# v8_psp.net
KiCad netlist of a schematic drawn in EAGLE
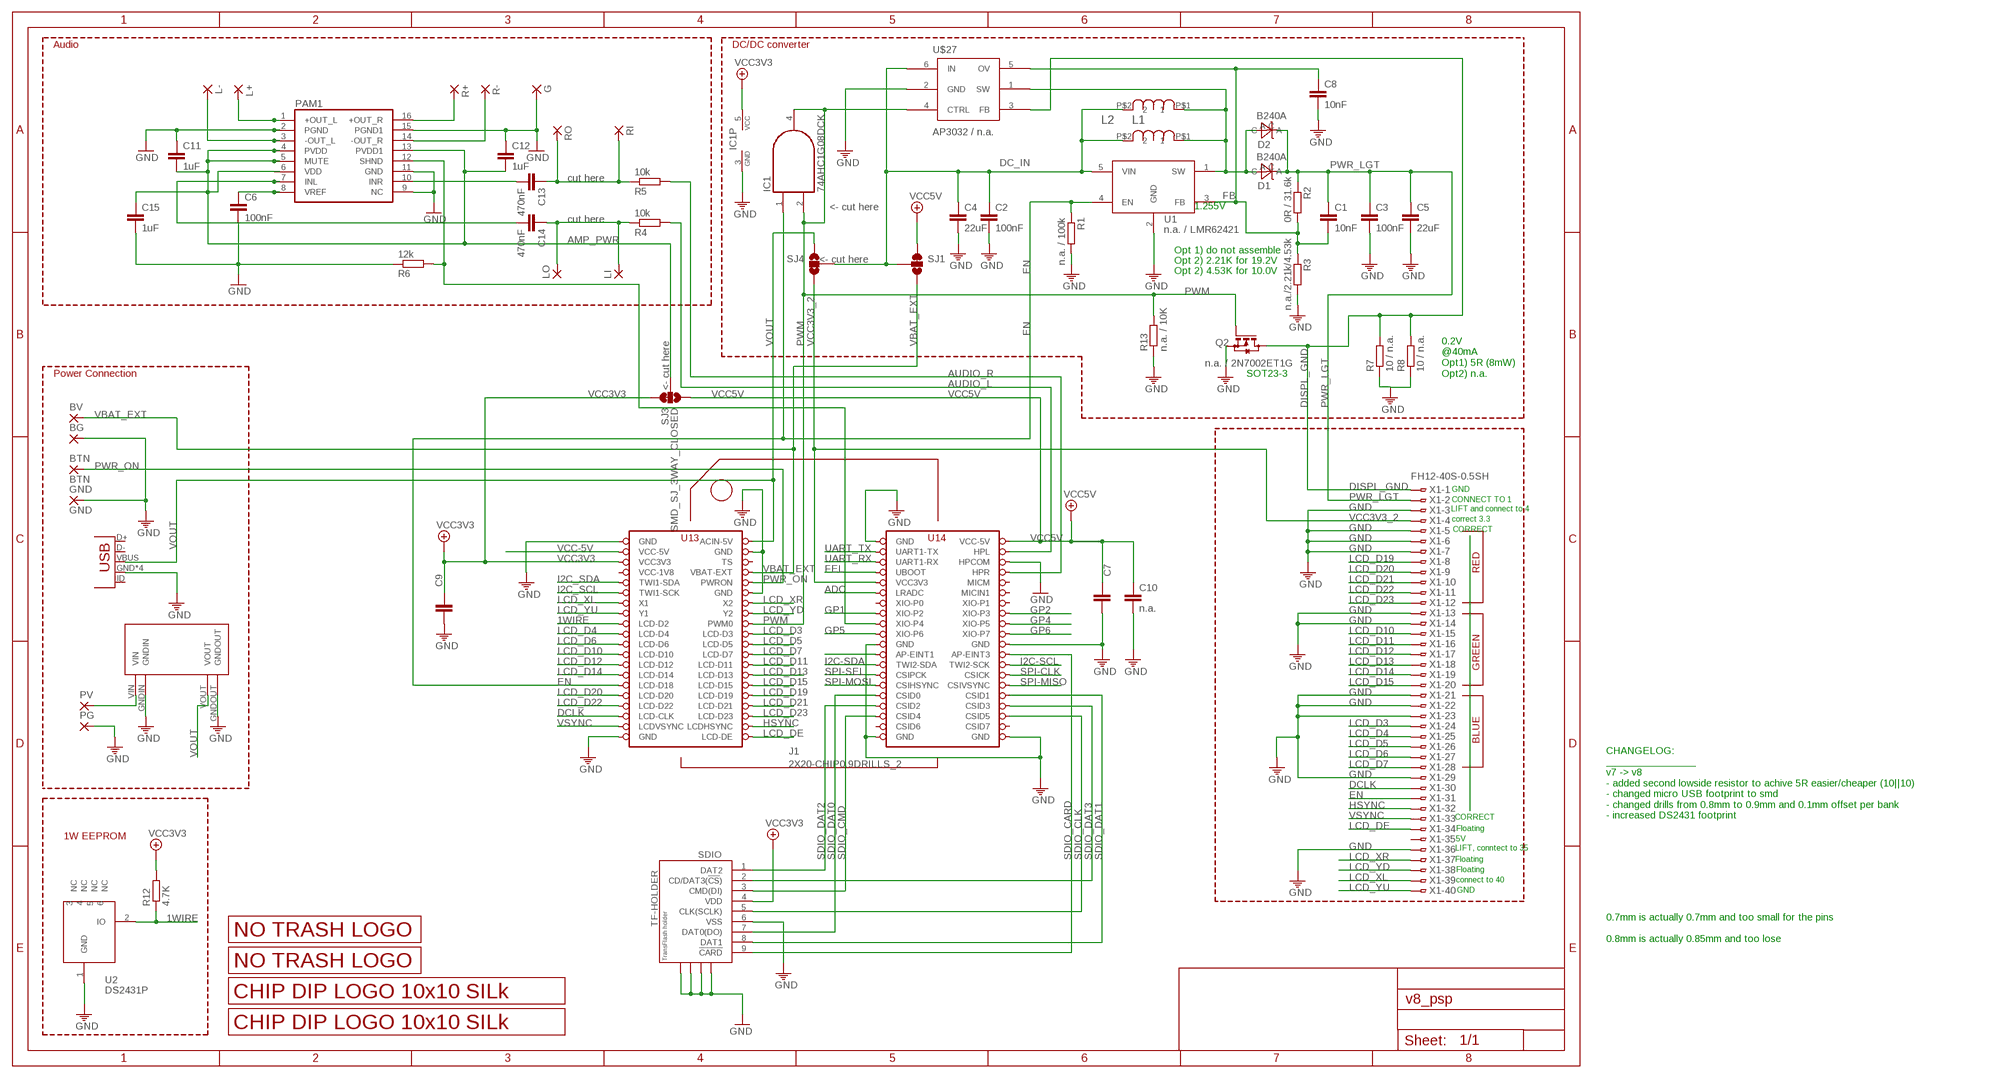
[diagram p0: schematic, sheet 1]

(export (version "E")
  (design (tool "Eeschema 10.0.6"))
  (components
    (comp (ref "BG")
      (value "1,6/0,8")
      (footprint "eagle-import:1,6_0,8")
      (libsource (lib "eagle-import") (part "1,6/0,8"))
    )
    (comp (ref "BTN")
      (value "BTN")
      (footprint "eagle-import:SMD1,27-2,54")
      (libsource (lib "eagle-import") (part "SMD2"))
    )
    (comp (ref "BV")
      (value "1,6/0,8")
      (footprint "eagle-import:1,6_0,8")
      (libsource (lib "eagle-import") (part "1,6/0,8"))
    )
    (comp (ref "C1")
      (value "10nF")
      (footprint "eagle-import:C0805")
      (libsource (lib "eagle-import") (part "C-EUC0805"))
    )
    (comp (ref "C2")
      (value "100nF")
      (footprint "eagle-import:C0805")
      (libsource (lib "eagle-import") (part "C-EUC0805"))
    )
    (comp (ref "C3")
      (value "100nF")
      (footprint "eagle-import:C0805")
      (libsource (lib "eagle-import") (part "C-EUC0805"))
    )
    (comp (ref "C4")
      (value "22uF")
      (footprint "eagle-import:C1206")
      (libsource (lib "eagle-import") (part "C-EUC1206"))
    )
    (comp (ref "C5")
      (value "22uF")
      (footprint "eagle-import:C1206")
      (libsource (lib "eagle-import") (part "C-EUC1206"))
    )
    (comp (ref "C6")
      (value "100nF")
      (footprint "eagle-import:C0805")
      (libsource (lib "eagle-import") (part "C-EUC0805"))
    )
    (comp (ref "C7")
      (value "n.a.")
      (footprint "eagle-import:C0805")
      (libsource (lib "eagle-import") (part "C-EUC0805"))
    )
    (comp (ref "C8")
      (value "10nF")
      (footprint "eagle-import:C0805")
      (libsource (lib "eagle-import") (part "C-EUC0805"))
    )
    (comp (ref "C9")
      (value "n.a.")
      (footprint "eagle-import:C0805")
      (libsource (lib "eagle-import") (part "C-EUC0805"))
    )
    (comp (ref "C10")
      (value "n.a.")
      (footprint "eagle-import:C0805")
      (libsource (lib "eagle-import") (part "C-EUC0805"))
    )
    (comp (ref "C11")
      (value "1uF")
      (footprint "eagle-import:C0805")
      (libsource (lib "eagle-import") (part "C-EUC0805"))
    )
    (comp (ref "C12")
      (value "1uF")
      (footprint "eagle-import:C0805")
      (libsource (lib "eagle-import") (part "C-EUC0805"))
    )
    (comp (ref "C13")
      (value "470nF")
      (footprint "eagle-import:C0805")
      (libsource (lib "eagle-import") (part "C-EUC0805"))
    )
    (comp (ref "C14")
      (value "470nF")
      (footprint "eagle-import:C0805")
      (libsource (lib "eagle-import") (part "C-EUC0805"))
    )
    (comp (ref "C15")
      (value "1uF")
      (footprint "eagle-import:C0805")
      (libsource (lib "eagle-import") (part "C-EUC0805"))
    )
    (comp (ref "D1")
      (value "B240A")
      (footprint "eagle-import:DO-214AC")
      (fields (field (name "MFG") "DIGIKEY") (field (name "VENDOR_PART_NUMBER") "B240A-13-F"))
      (libsource (lib "eagle-import") (part "DIODE_SCHTKY_B240"))
    )
    (comp (ref "D2")
      (value "B240A")
      (footprint "eagle-import:DO-214AC")
      (fields (field (name "MFG") "DIGIKEY") (field (name "VENDOR_PART_NUMBER") "B240A-13-F"))
      (libsource (lib "eagle-import") (part "DIODE_SCHTKY_B240"))
    )
    (comp (ref "G")
      (value "1,6/0,8")
      (footprint "eagle-import:1,6_0,8")
      (libsource (lib "eagle-import") (part "1,6/0,8"))
    )
    (comp (ref "GND")
      (value "GND")
      (footprint "eagle-import:SMD1,27-2,54")
      (libsource (lib "eagle-import") (part "SMD2"))
    )
    (comp (ref "IC1")
      (value "74AHC1G08DCK")
      (footprint "eagle-import:SC70-5")
      (libsource (lib "eagle-import") (part "741G08DCKAHC"))
    )
    (comp (ref "J1")
      (value "2X20-CHIP0.9DRILLS_2")
      (footprint "eagle-import:2X20CHIP_BANK_OFFSET_TH_0.9")
      (libsource (lib "eagle-import") (part "2X20-CHIP0.9DRILLS_2"))
    )
    (comp (ref "JP1")
      (value "USBMICRO_SMD")
      (footprint "eagle-import:USB-B-MICRO-SMD_V03")
      (libsource (lib "eagle-import") (part "USBMICRO_SMD"))
    )
    (comp (ref "L+")
      (value "1,6/0,8")
      (footprint "eagle-import:1,6_0,8")
      (libsource (lib "eagle-import") (part "1,6/0,8"))
    )
    (comp (ref "L-")
      (value "1,6/0,8")
      (footprint "eagle-import:1,6_0,8")
      (libsource (lib "eagle-import") (part "1,6/0,8"))
    )
    (comp (ref "L1")
      (value "SRN6045-100M")
      (footprint "eagle-import:SRN6045")
      (fields (field (name "MFG") "DIGIKEY"))
      (libsource (lib "eagle-import") (part "SRN6045-100M"))
    )
    (comp (ref "L2")
      (value "SRN6045-100M")
      (footprint "eagle-import:SRN6045")
      (fields (field (name "MFG") "DIGIKEY"))
      (libsource (lib "eagle-import") (part "SRN6045-100M"))
    )
    (comp (ref "LI")
      (value "1,6/0,8")
      (footprint "eagle-import:1,6_0,8")
      (libsource (lib "eagle-import") (part "1,6/0,8"))
    )
    (comp (ref "LO")
      (value "1,6/0,8")
      (footprint "eagle-import:1,6_0,8")
      (libsource (lib "eagle-import") (part "1,6/0,8"))
    )
    (comp (ref "PAM1")
      (value "PAM8403")
      (footprint "eagle-import:SOP-16")
      (libsource (lib "eagle-import") (part "PAM8403"))
    )
    (comp (ref "PG")
      (value "1,6/0,8")
      (footprint "eagle-import:1,6_0,8")
      (libsource (lib "eagle-import") (part "1,6/0,8"))
    )
    (comp (ref "PV")
      (value "1,6/0,8")
      (footprint "eagle-import:1,6_0,8")
      (libsource (lib "eagle-import") (part "1,6/0,8"))
    )
    (comp (ref "Q2")
      (value "n.a. / 2N7002ET1G")
      (footprint "eagle-import:SOT23")
      (libsource (lib "eagle-import") (part "BSS123"))
    )
    (comp (ref "R+")
      (value "1,6/0,8")
      (footprint "eagle-import:1,6_0,8")
      (libsource (lib "eagle-import") (part "1,6/0,8"))
    )
    (comp (ref "R-")
      (value "1,6/0,8")
      (footprint "eagle-import:1,6_0,8")
      (libsource (lib "eagle-import") (part "1,6/0,8"))
    )
    (comp (ref "R1")
      (value "n.a. / 100k")
      (footprint "eagle-import:M0805")
      (libsource (lib "eagle-import") (part "R-EU_M0805"))
    )
    (comp (ref "R2")
      (value "0R / 31.6k")
      (footprint "eagle-import:M0805")
      (libsource (lib "eagle-import") (part "R-EU_M0805"))
    )
    (comp (ref "R3")
      (value "n.a./2.21k/4.53k")
      (footprint "eagle-import:M0805")
      (libsource (lib "eagle-import") (part "R-EU_M0805"))
    )
    (comp (ref "R4")
      (value "10k")
      (footprint "eagle-import:R0805")
      (libsource (lib "eagle-import") (part "R-EU_R0805"))
    )
    (comp (ref "R5")
      (value "10k")
      (footprint "eagle-import:R0805")
      (libsource (lib "eagle-import") (part "R-EU_R0805"))
    )
    (comp (ref "R6")
      (value "12k")
      (footprint "eagle-import:R0805")
      (libsource (lib "eagle-import") (part "R-EU_R0805"))
    )
    (comp (ref "R7")
      (value "10 / n.a.")
      (footprint "eagle-import:M0805")
      (libsource (lib "eagle-import") (part "R-EU_M0805"))
    )
    (comp (ref "R8")
      (value "10 / n.a.")
      (footprint "eagle-import:M0805")
      (libsource (lib "eagle-import") (part "R-EU_M0805"))
    )
    (comp (ref "R12")
      (value "4.7K")
      (footprint "eagle-import:M0805")
      (libsource (lib "eagle-import") (part "R-EU_M0805"))
    )
    (comp (ref "R13")
      (value "n.a. / 10K")
      (footprint "eagle-import:M0805")
      (libsource (lib "eagle-import") (part "R-EU_M0805"))
    )
    (comp (ref "RI")
      (value "1,6/0,8")
      (footprint "eagle-import:1,6_0,8")
      (libsource (lib "eagle-import") (part "1,6/0,8"))
    )
    (comp (ref "RO")
      (value "1,6/0,8")
      (footprint "eagle-import:1,6_0,8")
      (libsource (lib "eagle-import") (part "1,6/0,8"))
    )
    (comp (ref "SDIO")
      (value "TF-HOLDER")
      (footprint "eagle-import:TF-PULL")
      (libsource (lib "eagle-import") (part "TF-HOLDER"))
    )
    (comp (ref "SJ1")
      (value "SMD_SJ_3WAY_CLOSED")
      (footprint "eagle-import:SMD_SJ_3WAY_CLOSED")
      (libsource (lib "eagle-import") (part "SMD_SJ_3WAY_CLOSED"))
    )
    (comp (ref "SJ3")
      (value "SMD_SJ_3WAY_CLOSED")
      (footprint "eagle-import:SMD_SJ_3WAY_CLOSED")
      (libsource (lib "eagle-import") (part "SMD_SJ_3WAY_CLOSED"))
    )
    (comp (ref "SJ4")
      (value "SMD_SJ_3WAY_OPENT")
      (footprint "eagle-import:SMD_SJ_3WAY_OPEN")
      (libsource (lib "eagle-import") (part "SMD_SJ_3WAY_OPENT"))
    )
    (comp (ref "U$2")
      (value "LOGO_10X10_SILK")
      (footprint "eagle-import:LOGO2_10X10_SILK")
      (libsource (lib "eagle-import") (part "LOGO_10X10_SILK"))
    )
    (comp (ref "U$3")
      (value "LOGO_NO_TRASHROHS")
      (footprint "eagle-import:LOGO_ROHS_SYM")
      (libsource (lib "eagle-import") (part "LOGO_NO_TRASHROHS"))
    )
    (comp (ref "U$4")
      (value "LOGO_NO_TRASHNO_TRASH")
      (footprint "eagle-import:LOGO_ROHS_NO_TRASH")
      (libsource (lib "eagle-import") (part "LOGO_NO_TRASHNO_TRASH"))
    )
    (comp (ref "U$5")
      (value "LOGO_10X10_SILK")
      (footprint "eagle-import:LOGO2_10X10_SILK")
      (libsource (lib "eagle-import") (part "LOGO_10X10_SILK"))
    )
    (comp (ref "U$10")
      (value "MP1584EN_FRAMELESS")
      (footprint "eagle-import:MP1584EN_FRAMELESS")
      (libsource (lib "eagle-import") (part "MP1584EN_FRAMELESS"))
    )
    (comp (ref "U$27")
      (value "AP3032 / n.a.")
      (footprint "eagle-import:SOT23-6")
      (libsource (lib "eagle-import") (part "AP3032"))
    )
    (comp (ref "U1")
      (value "n.a. / LMR62421")
      (footprint "eagle-import:SOT23-5")
      (fields (field (name "MFG") "DIGIKEY") (field (name "VENDOR_PART_NUMBER") "LMR62421XMFE/NOPB"))
      (libsource (lib "eagle-import") (part "LMR62421"))
    )
    (comp (ref "U2")
      (value "DS2431P")
      (footprint "eagle-import:TSOC6")
      (fields (field (name "MFG") "DIGIKEY") (field (name "VENDOR_PART_NUMBER") "DS2431P+T&R"))
      (libsource (lib "eagle-import") (part "DS2431P"))
    )
    (comp (ref "X1")
      (value "FH12-40S-0.5SH")
      (footprint "eagle-import:FH12-40S-0.5SH")
      (fields (field (name "MFG") "DIGIKEY") (field (name "VENDOR_PART_NUMBER") "FH12-40S-0.5SH(55)"))
      (libsource (lib "eagle-import") (part "FH12-40S-0.5SH"))
    )
  )
  (nets
    (net (code "1") (name "/1WIRE") (class "Default")
      (node (ref "J1") (pin "LCD-D2") (pinfunction "LCD-D2_LCD-D2") (pintype "passive"))
      (node (ref "R12") (pin "1") (pinfunction "1_1") (pintype "passive"))
      (node (ref "U2") (pin "2") (pinfunction "IO_2") (pintype "bidirectional"))
    )
    (net (code "2") (name "/ADC") (class "Default")
      (node (ref "J1") (pin "LRADC") (pinfunction "LRADC_LRADC") (pintype "passive"))
    )
    (net (code "3") (name "/AMP_PWR") (class "Default")
      (node (ref "C11") (pin "2") (pinfunction "2_2") (pintype "passive"))
      (node (ref "C12") (pin "2") (pinfunction "2_2") (pintype "passive"))
      (node (ref "C15") (pin "1") (pinfunction "1_1") (pintype "passive"))
      (node (ref "PAM1") (pin "13") (pinfunction "PVDD1_13") (pintype "output"))
      (node (ref "PAM1") (pin "4") (pinfunction "PVDD_4") (pintype "input"))
      (node (ref "PAM1") (pin "5") (pinfunction "MUTE_5") (pintype "input"))
      (node (ref "PAM1") (pin "6") (pinfunction "VDD_6") (pintype "input"))
      (node (ref "SJ3") (pin "2") (pinfunction "2_2") (pintype "passive"))
    )
    (net (code "4") (name "/AUDIO_L") (class "Default")
      (node (ref "J1") (pin "HPL") (pinfunction "HPL_HPL") (pintype "passive"))
      (node (ref "R4") (pin "2") (pinfunction "2_2") (pintype "passive"))
    )
    (net (code "5") (name "/AUDIO_R") (class "Default")
      (node (ref "J1") (pin "HPR") (pinfunction "HPR_HPR") (pintype "passive"))
      (node (ref "R5") (pin "2") (pinfunction "2_2") (pintype "passive"))
    )
    (net (code "6") (name "/DCLK") (class "Default")
      (node (ref "J1") (pin "LCD-CLK") (pinfunction "LCD-CLK_LCD-CLK") (pintype "passive"))
      (node (ref "X1") (pin "30") (pinfunction "1_30") (pintype "passive"))
    )
    (net (code "7") (name "/DC_IN") (class "Default")
      (node (ref "C2") (pin "1") (pinfunction "1_1") (pintype "passive"))
      (node (ref "C4") (pin "1") (pinfunction "1_1") (pintype "passive"))
      (node (ref "L1") (pin "P$2") (pinfunction "2_P$2") (pintype "passive"))
      (node (ref "L2") (pin "P$2") (pinfunction "2_P$2") (pintype "passive"))
      (node (ref "SJ1") (pin "2") (pinfunction "2_2") (pintype "passive"))
      (node (ref "SJ4") (pin "2") (pinfunction "2_2") (pintype "passive"))
      (node (ref "U$27") (pin "6") (pinfunction "IN_6") (pintype "power_in"))
      (node (ref "U1") (pin "5") (pinfunction "VIN_5") (pintype "bidirectional"))
    )
    (net (code "8") (name "/DISPL_GND") (class "Default")
      (node (ref "Q2") (pin "3") (pinfunction "D_3") (pintype "passive"))
      (node (ref "R7") (pin "2") (pinfunction "2_2") (pintype "passive"))
      (node (ref "R8") (pin "2") (pinfunction "2_2") (pintype "passive"))
      (node (ref "U$27") (pin "3") (pinfunction "FB_3") (pintype "passive"))
      (node (ref "X1") (pin "1") (pinfunction "1_1") (pintype "passive"))
    )
    (net (code "9") (name "/EN") (class "Default")
      (node (ref "IC1") (pin "1") (pinfunction "I0_1") (pintype "input"))
      (node (ref "J1") (pin "LCD-D18") (pinfunction "LCD-D18_LCD-D18") (pintype "passive"))
      (node (ref "R1") (pin "1") (pinfunction "1_1") (pintype "passive"))
      (node (ref "U1") (pin "4") (pinfunction "EN_4") (pintype "bidirectional"))
      (node (ref "X1") (pin "31") (pinfunction "1_31") (pintype "passive"))
    )
    (net (code "10") (name "/FB") (class "Default")
      (node (ref "C1") (pin "2") (pinfunction "2_2") (pintype "passive"))
      (node (ref "C8") (pin "1") (pinfunction "1_1") (pintype "passive"))
      (node (ref "R2") (pin "2") (pinfunction "2_2") (pintype "passive"))
      (node (ref "R3") (pin "1") (pinfunction "1_1") (pintype "passive"))
      (node (ref "U$27") (pin "5") (pinfunction "OV_5") (pintype "power_in"))
      (node (ref "U1") (pin "3") (pinfunction "FB_3") (pintype "bidirectional"))
    )
    (net (code "11") (name "/FEL") (class "Default")
      (node (ref "J1") (pin "FEL") (pinfunction "UBOOT_FEL") (pintype "passive"))
    )
    (net (code "12") (name "/GP1") (class "Default")
      (node (ref "J1") (pin "XIO-P2") (pinfunction "XIO-P2_XIO-P2") (pintype "passive"))
    )
    (net (code "13") (name "/GP2") (class "Default")
      (node (ref "J1") (pin "XIO-P3") (pinfunction "XIO-P3_XIO-P3") (pintype "passive"))
    )
    (net (code "14") (name "/GP4") (class "Default")
      (node (ref "J1") (pin "XIO-P5") (pinfunction "XIO-P5_XIO-P5") (pintype "passive"))
    )
    (net (code "15") (name "/GP5") (class "Default")
      (node (ref "J1") (pin "XIO-P6") (pinfunction "XIO-P6_XIO-P6") (pintype "passive"))
    )
    (net (code "16") (name "/GP6") (class "Default")
      (node (ref "J1") (pin "XIO-P7") (pinfunction "XIO-P7_XIO-P7") (pintype "passive"))
    )
    (net (code "17") (name "/HSYNC") (class "Default")
      (node (ref "J1") (pin "LCD-HSYNC") (pinfunction "LCDHSYNC_LCD-HSYNC") (pintype "passive"))
      (node (ref "X1") (pin "32") (pinfunction "1_32") (pintype "passive"))
    )
    (net (code "18") (name "/I2C-SCL") (class "Default")
      (node (ref "J1") (pin "TWI2-SCK") (pinfunction "TWI2-SCK_TWI2-SCK") (pintype "passive"))
    )
    (net (code "19") (name "/I2C-SDA") (class "Default")
      (node (ref "J1") (pin "TWI2-SDA") (pinfunction "TWI2-SDA_TWI2-SDA") (pintype "passive"))
    )
    (net (code "20") (name "/I2C_SCL") (class "Default")
      (node (ref "J1") (pin "TWI1-SCK") (pinfunction "TWI1-SCK_TWI1-SCK") (pintype "passive"))
    )
    (net (code "21") (name "/I2C_SDA") (class "Default")
      (node (ref "J1") (pin "TWI1-SDA") (pinfunction "TWI1-SDA_TWI1-SDA") (pintype "passive"))
    )
    (net (code "22") (name "/LCD_D3") (class "Default")
      (node (ref "J1") (pin "LCD-D3") (pinfunction "LCD-D3_LCD-D3") (pintype "passive"))
      (node (ref "X1") (pin "24") (pinfunction "1_24") (pintype "passive"))
    )
    (net (code "23") (name "/LCD_D4") (class "Default")
      (node (ref "J1") (pin "LCD-D4") (pinfunction "LCD-D4_LCD-D4") (pintype "passive"))
      (node (ref "X1") (pin "25") (pinfunction "1_25") (pintype "passive"))
    )
    (net (code "24") (name "/LCD_D5") (class "Default")
      (node (ref "J1") (pin "LCD-D5") (pinfunction "LCD-D5_LCD-D5") (pintype "passive"))
      (node (ref "X1") (pin "26") (pinfunction "1_26") (pintype "passive"))
    )
    (net (code "25") (name "/LCD_D6") (class "Default")
      (node (ref "J1") (pin "LCD-D6") (pinfunction "LCD-D6_LCD-D6") (pintype "passive"))
      (node (ref "X1") (pin "27") (pinfunction "1_27") (pintype "passive"))
    )
    (net (code "26") (name "/LCD_D7") (class "Default")
      (node (ref "J1") (pin "LCD-D7") (pinfunction "LCD-D7_LCD-D7") (pintype "passive"))
      (node (ref "X1") (pin "28") (pinfunction "1_28") (pintype "passive"))
    )
    (net (code "27") (name "/LCD_D10") (class "Default")
      (node (ref "J1") (pin "LCD-D10") (pinfunction "LCD-D10_LCD-D10") (pintype "passive"))
      (node (ref "X1") (pin "15") (pinfunction "1_15") (pintype "passive"))
    )
    (net (code "28") (name "/LCD_D11") (class "Default")
      (node (ref "J1") (pin "LCD-D11") (pinfunction "LCD-D11_LCD-D11") (pintype "passive"))
      (node (ref "X1") (pin "16") (pinfunction "1_16") (pintype "passive"))
    )
    (net (code "29") (name "/LCD_D12") (class "Default")
      (node (ref "J1") (pin "LCD-D12") (pinfunction "LCD-D12_LCD-D12") (pintype "passive"))
      (node (ref "X1") (pin "17") (pinfunction "1_17") (pintype "passive"))
    )
    (net (code "30") (name "/LCD_D13") (class "Default")
      (node (ref "J1") (pin "LCD-D13") (pinfunction "LCD-D13_LCD-D13") (pintype "passive"))
      (node (ref "X1") (pin "18") (pinfunction "1_18") (pintype "passive"))
    )
    (net (code "31") (name "/LCD_D14") (class "Default")
      (node (ref "J1") (pin "LCD-D14") (pinfunction "LCD-D14_LCD-D14") (pintype "passive"))
      (node (ref "X1") (pin "19") (pinfunction "1_19") (pintype "passive"))
    )
    (net (code "32") (name "/LCD_D15") (class "Default")
      (node (ref "J1") (pin "LCD-D15") (pinfunction "LCD-D15_LCD-D15") (pintype "passive"))
      (node (ref "X1") (pin "20") (pinfunction "1_20") (pintype "passive"))
    )
    (net (code "33") (name "/LCD_D19") (class "Default")
      (node (ref "J1") (pin "LCD-D19") (pinfunction "LCD-D19_LCD-D19") (pintype "passive"))
      (node (ref "X1") (pin "8") (pinfunction "1_8") (pintype "passive"))
    )
    (net (code "34") (name "/LCD_D20") (class "Default")
      (node (ref "J1") (pin "LCD-D20") (pinfunction "LCD-D20_LCD-D20") (pintype "passive"))
      (node (ref "X1") (pin "9") (pinfunction "1_9") (pintype "passive"))
    )
    (net (code "35") (name "/LCD_D21") (class "Default")
      (node (ref "J1") (pin "LCD-D21") (pinfunction "LCD-D21_LCD-D21") (pintype "passive"))
      (node (ref "X1") (pin "10") (pinfunction "1_10") (pintype "passive"))
    )
    (net (code "36") (name "/LCD_D22") (class "Default")
      (node (ref "J1") (pin "LCD-D22") (pinfunction "LCD-D22_LCD-D22") (pintype "passive"))
      (node (ref "X1") (pin "11") (pinfunction "1_11") (pintype "passive"))
    )
    (net (code "37") (name "/LCD_D23") (class "Default")
      (node (ref "J1") (pin "LCD-D23") (pinfunction "LCD-D23_LCD-D23") (pintype "passive"))
      (node (ref "X1") (pin "12") (pinfunction "1_12") (pintype "passive"))
    )
    (net (code "38") (name "/LCD_DE") (class "Default")
      (node (ref "J1") (pin "LCD-DE") (pinfunction "LCD-DE_LCD-DE") (pintype "passive"))
      (node (ref "X1") (pin "34") (pinfunction "1_34") (pintype "passive"))
    )
    (net (code "39") (name "/LCD_XL") (class "Default")
      (node (ref "J1") (pin "X1") (pinfunction "X1_X1") (pintype "passive"))
      (node (ref "X1") (pin "39") (pinfunction "1_39") (pintype "passive"))
    )
    (net (code "40") (name "/LCD_XR") (class "Default")
      (node (ref "J1") (pin "X2") (pinfunction "X2_X2") (pintype "passive"))
      (node (ref "X1") (pin "37") (pinfunction "1_37") (pintype "passive"))
    )
    (net (code "41") (name "/LCD_YD") (class "Default")
      (node (ref "J1") (pin "Y2") (pinfunction "Y2_Y2") (pintype "passive"))
      (node (ref "X1") (pin "38") (pinfunction "1_38") (pintype "passive"))
    )
    (net (code "42") (name "/LCD_YU") (class "Default")
      (node (ref "J1") (pin "Y1") (pinfunction "Y1_Y1") (pintype "passive"))
      (node (ref "X1") (pin "40") (pinfunction "1_40") (pintype "passive"))
    )
    (net (code "43") (name "/PWM") (class "Default")
      (node (ref "IC1") (pin "2") (pinfunction "I1_2") (pintype "input"))
      (node (ref "IC1") (pin "4") (pinfunction "O_4") (pintype "output"))
      (node (ref "J1") (pin "PWM0") (pinfunction "PWM0_PWM0") (pintype "passive"))
      (node (ref "Q2") (pin "1") (pinfunction "G_1") (pintype "passive"))
      (node (ref "R13") (pin "2") (pinfunction "2_2") (pintype "passive"))
      (node (ref "U$27") (pin "4") (pinfunction "CTRL_4") (pintype "input"))
    )
    (net (code "44") (name "/PWR_LGT") (class "Default")
      (node (ref "C1") (pin "1") (pinfunction "1_1") (pintype "passive"))
      (node (ref "C3") (pin "1") (pinfunction "1_1") (pintype "passive"))
      (node (ref "C5") (pin "1") (pinfunction "1_1") (pintype "passive"))
      (node (ref "D1") (pin "C") (pinfunction "C_C") (pintype "bidirectional"))
      (node (ref "D2") (pin "C") (pinfunction "C_C") (pintype "bidirectional"))
      (node (ref "R2") (pin "1") (pinfunction "1_1") (pintype "passive"))
      (node (ref "X1") (pin "2") (pinfunction "1_2") (pintype "passive"))
    )
    (net (code "45") (name "/PWR_ON") (class "Default")
      (node (ref "BTN") (pin "1") (pinfunction "P_1") (pintype "passive"))
      (node (ref "J1") (pin "PWRON") (pinfunction "PWRON_PWRON") (pintype "passive"))
    )
    (net (code "46") (name "/SDIO_CARD") (class "Default")
      (node (ref "J1") (pin "AP-EINT3") (pinfunction "AP-EINT3_AP-EINT3") (pintype "passive"))
      (node (ref "SDIO") (pin "9") (pinfunction "~{CARD}_9") (pintype "passive"))
    )
    (net (code "47") (name "/SDIO_CLK") (class "Default")
      (node (ref "J1") (pin "CSID5") (pinfunction "CSID5_CSID5") (pintype "passive"))
      (node (ref "SDIO") (pin "5") (pinfunction "CLK(SCLK)_5") (pintype "input"))
    )
    (net (code "48") (name "/SDIO_CMD") (class "Default")
      (node (ref "J1") (pin "CSID4") (pinfunction "CSID4_CSID4") (pintype "passive"))
      (node (ref "SDIO") (pin "3") (pinfunction "CMD(DI)_3") (pintype "bidirectional"))
    )
    (net (code "49") (name "/SDIO_DAT0") (class "Default")
      (node (ref "J1") (pin "CSID0") (pinfunction "CSID0_CSID0") (pintype "passive"))
      (node (ref "SDIO") (pin "7") (pinfunction "DAT0(DO)_7") (pintype "bidirectional"))
    )
    (net (code "50") (name "/SDIO_DAT1") (class "Default")
      (node (ref "J1") (pin "CSID1") (pinfunction "CSID1_CSID1") (pintype "passive"))
      (node (ref "SDIO") (pin "8") (pinfunction "DAT1_8") (pintype "bidirectional"))
    )
    (net (code "51") (name "/SDIO_DAT2") (class "Default")
      (node (ref "J1") (pin "CSID2") (pinfunction "CSID2_CSID2") (pintype "passive"))
      (node (ref "SDIO") (pin "1") (pinfunction "DAT2_1") (pintype "bidirectional"))
    )
    (net (code "52") (name "/SDIO_DAT3") (class "Default")
      (node (ref "J1") (pin "CSID3") (pinfunction "CSID3_CSID3") (pintype "passive"))
      (node (ref "SDIO") (pin "2") (pinfunction "CD/DAT3(~{CS})_2") (pintype "bidirectional"))
    )
    (net (code "53") (name "/SPI-CLK") (class "Default")
      (node (ref "J1") (pin "CSICK") (pinfunction "CSICK_CSICK") (pintype "passive"))
    )
    (net (code "54") (name "/SPI-MISO") (class "Default")
      (node (ref "J1") (pin "CSIVSYNC") (pinfunction "CSIVSYNC_CSIVSYNC") (pintype "passive"))
    )
    (net (code "55") (name "/SPI-MOSI") (class "Default")
      (node (ref "J1") (pin "CSIHSYNC") (pinfunction "CSIHSYNC_CSIHSYNC") (pintype "passive"))
    )
    (net (code "56") (name "/SPI-SEL") (class "Default")
      (node (ref "J1") (pin "CSIPCK") (pinfunction "CSIPCK_CSIPCK") (pintype "passive"))
    )
    (net (code "57") (name "/UART_RX") (class "Default")
      (node (ref "J1") (pin "UART1-RX") (pinfunction "UART1-RX_UART1-RX") (pintype "passive"))
    )
    (net (code "58") (name "/UART_TX") (class "Default")
      (node (ref "J1") (pin "UART1-TX") (pinfunction "UART1-TX_UART1-TX") (pintype "passive"))
    )
    (net (code "59") (name "/VBAT_EXT") (class "Default")
      (node (ref "BV") (pin "1") (pinfunction "P_1") (pintype "passive"))
      (node (ref "J1") (pin "BAT") (pinfunction "VBAT-EXT_BAT") (pintype "passive"))
      (node (ref "SJ1") (pin "3") (pinfunction "3_3") (pintype "passive"))
    )
    (net (code "60") (name "/VCC-1V8") (class "Default")
      (node (ref "J1") (pin "VCC1V8") (pinfunction "VCC-1V8_VCC1V8") (pintype "power_in"))
    )
    (net (code "61") (name "/VCC-5V") (class "Default")
      (node (ref "J1") (pin "VCC5V@0") (pinfunction "VCC-5V_VCC5V@0") (pintype "power_in"))
    )
    (net (code "62") (name "/VCC3V3_2") (class "Default")
      (node (ref "J1") (pin "VCC3V3@1") (pinfunction "VCC3V3_VCC3V3@1") (pintype "power_in"))
      (node (ref "SJ4") (pin "3") (pinfunction "3_3") (pintype "passive"))
      (node (ref "X1") (pin "4") (pinfunction "1_4") (pintype "passive"))
    )
    (net (code "63") (name "/VOUT") (class "Default")
      (node (ref "J1") (pin "CHG-IN") (pinfunction "ACIN-5V_CHG-IN") (pintype "passive"))
      (node (ref "JP1") (pin "VBUS") (pinfunction "VBUS_VBUS") (pintype "bidirectional"))
      (node (ref "SJ4") (pin "1") (pinfunction "1_1") (pintype "passive"))
      (node (ref "U$10") (pin "VOUT") (pinfunction "VOUT_VOUT") (pintype "power_in"))
    )
    (net (code "64") (name "/VSYNC") (class "Default")
      (node (ref "J1") (pin "LCD-VSYNC") (pinfunction "LCDVSYNC_LCD-VSYNC") (pintype "passive"))
      (node (ref "X1") (pin "33") (pinfunction "1_33") (pintype "passive"))
    )
    (net (code "65") (name "GND") (class "Default")
      (node (ref "BG") (pin "1") (pinfunction "P_1") (pintype "passive"))
      (node (ref "C10") (pin "2") (pinfunction "2_2") (pintype "passive"))
      (node (ref "C11") (pin "1") (pinfunction "1_1") (pintype "passive"))
      (node (ref "C12") (pin "1") (pinfunction "1_1") (pintype "passive"))
      (node (ref "C15") (pin "2") (pinfunction "2_2") (pintype "passive"))
      (node (ref "C2") (pin "2") (pinfunction "2_2") (pintype "passive"))
      (node (ref "C3") (pin "2") (pinfunction "2_2") (pintype "passive"))
      (node (ref "C4") (pin "2") (pinfunction "2_2") (pintype "passive"))
      (node (ref "C5") (pin "2") (pinfunction "2_2") (pintype "passive"))
      (node (ref "C6") (pin "2") (pinfunction "2_2") (pintype "passive"))
      (node (ref "C7") (pin "2") (pinfunction "2_2") (pintype "passive"))
      (node (ref "C8") (pin "2") (pinfunction "2_2") (pintype "passive"))
      (node (ref "C9") (pin "2") (pinfunction "2_2") (pintype "passive"))
      (node (ref "G") (pin "1") (pinfunction "P_1") (pintype "passive"))
      (node (ref "GND") (pin "1") (pinfunction "P_1") (pintype "passive"))
      (node (ref "IC1") (pin "3") (pinfunction "GND_3") (pintype "power_in"))
      (node (ref "J1") (pin "GND@1") (pinfunction "GND_GND@1") (pintype "power_in"))
      (node (ref "J1") (pin "GND@10") (pinfunction "GND_GND@10") (pintype "power_in"))
      (node (ref "J1") (pin "GND@2") (pinfunction "GND_GND@2") (pintype "power_in"))
      (node (ref "J1") (pin "GND@3") (pinfunction "GND_GND@3") (pintype "power_in"))
      (node (ref "J1") (pin "GND@4") (pinfunction "GND_GND@4") (pintype "power_in"))
      (node (ref "J1") (pin "GND@5") (pinfunction "GND_GND@5") (pintype "power_in"))
      (node (ref "J1") (pin "GND@6") (pinfunction "GND_GND@6") (pintype "power_in"))
      (node (ref "J1") (pin "GND@7") (pinfunction "GND_GND@7") (pintype "power_in"))
      (node (ref "J1") (pin "GND@8") (pinfunction "GND_GND@8") (pintype "power_in"))
      (node (ref "J1") (pin "HPCOM") (pinfunction "HPCOM_HPCOM") (pintype "passive"))
      (node (ref "JP1") (pin "GND") (pinfunction "GND_GND") (pintype "bidirectional"))
      (node (ref "JP1") (pin "SHIELD1") (pinfunction "GND_SHIELD1") (pintype "bidirectional"))
      (node (ref "JP1") (pin "SHIELD2") (pinfunction "GND_SHIELD2") (pintype "bidirectional"))
      (node (ref "JP1") (pin "SHIELD3") (pinfunction "GND_SHIELD3") (pintype "bidirectional"))
      (node (ref "PAM1") (pin "11") (pinfunction "GND_11") (pintype "output"))
      (node (ref "PAM1") (pin "15") (pinfunction "PGND1_15") (pintype "output"))
      (node (ref "PAM1") (pin "2") (pinfunction "PGND_2") (pintype "input"))
      (node (ref "PAM1") (pin "9") (pinfunction "NC_9") (pintype "output"))
      (node (ref "PG") (pin "1") (pinfunction "P_1") (pintype "passive"))
      (node (ref "Q2") (pin "2") (pinfunction "S_2") (pintype "passive"))
      (node (ref "R1") (pin "2") (pinfunction "2_2") (pintype "passive"))
      (node (ref "R13") (pin "1") (pinfunction "1_1") (pintype "passive"))
      (node (ref "R3") (pin "2") (pinfunction "2_2") (pintype "passive"))
      (node (ref "R6") (pin "1") (pinfunction "1_1") (pintype "passive"))
      (node (ref "R7") (pin "1") (pinfunction "1_1") (pintype "passive"))
      (node (ref "R8") (pin "1") (pinfunction "1_1") (pintype "passive"))
      (node (ref "SDIO") (pin "6") (pinfunction "VSS_6") (pintype "power_in"))
      (node (ref "SDIO") (pin "S1") (pinfunction "S1_S1") (pintype "passive"))
      (node (ref "SDIO") (pin "S2") (pinfunction "S2_S2") (pintype "passive"))
      (node (ref "SDIO") (pin "S3") (pinfunction "S3_S3") (pintype "passive"))
      (node (ref "SDIO") (pin "S4") (pinfunction "S4_S4") (pintype "passive"))
      (node (ref "U$10") (pin "GNDIN") (pinfunction "GNDIN_GNDIN") (pintype "power_in"))
      (node (ref "U$10") (pin "GNDOUT") (pinfunction "GNDOUT_GNDOUT") (pintype "power_in"))
      (node (ref "U$27") (pin "2") (pinfunction "GND_2") (pintype "power_in"))
      (node (ref "U1") (pin "2") (pinfunction "GND_2") (pintype "bidirectional"))
      (node (ref "U2") (pin "1") (pinfunction "GND_1") (pintype "bidirectional"))
      (node (ref "X1") (pin "13") (pinfunction "1_13") (pintype "passive"))
      (node (ref "X1") (pin "14") (pinfunction "1_14") (pintype "passive"))
      (node (ref "X1") (pin "21") (pinfunction "1_21") (pintype "passive"))
      (node (ref "X1") (pin "22") (pinfunction "1_22") (pintype "passive"))
      (node (ref "X1") (pin "23") (pinfunction "1_23") (pintype "passive"))
      (node (ref "X1") (pin "29") (pinfunction "1_29") (pintype "passive"))
      (node (ref "X1") (pin "3") (pinfunction "1_3") (pintype "passive"))
      (node (ref "X1") (pin "36") (pinfunction "1_36") (pintype "passive"))
      (node (ref "X1") (pin "5") (pinfunction "1_5") (pintype "passive"))
      (node (ref "X1") (pin "6") (pinfunction "1_6") (pintype "passive"))
      (node (ref "X1") (pin "7") (pinfunction "1_7") (pintype "passive"))
    )
    (net (code "66") (name "Net-(L+-P)") (class "Default")
      (node (ref "L+") (pin "1") (pinfunction "P_1") (pintype "passive"))
      (node (ref "PAM1") (pin "1") (pinfunction "+OUT_L_1") (pintype "input"))
    )
    (net (code "67") (name "Net-(L--P)") (class "Default")
      (node (ref "L-") (pin "1") (pinfunction "P_1") (pintype "passive"))
      (node (ref "PAM1") (pin "3") (pinfunction "-OUT_L_3") (pintype "input"))
    )
    (net (code "68") (name "Net-(L1-1)") (class "Default")
      (node (ref "D1") (pin "A") (pinfunction "A_A") (pintype "bidirectional"))
      (node (ref "D2") (pin "A") (pinfunction "A_A") (pintype "bidirectional"))
      (node (ref "L1") (pin "P$1") (pinfunction "1_P$1") (pintype "passive"))
      (node (ref "L2") (pin "P$1") (pinfunction "1_P$1") (pintype "passive"))
      (node (ref "U$27") (pin "1") (pinfunction "SW_1") (pintype "power_in"))
      (node (ref "U1") (pin "1") (pinfunction "SW_1") (pintype "bidirectional"))
    )
    (net (code "69") (name "Net-(LI-P)") (class "Default")
      (node (ref "C14") (pin "1") (pinfunction "1_1") (pintype "passive"))
      (node (ref "LI") (pin "1") (pinfunction "P_1") (pintype "passive"))
      (node (ref "LO") (pin "1") (pinfunction "P_1") (pintype "passive"))
      (node (ref "R4") (pin "1") (pinfunction "1_1") (pintype "passive"))
    )
    (net (code "70") (name "Net-(PAM1-+OUT_R)") (class "Default")
      (node (ref "PAM1") (pin "16") (pinfunction "+OUT_R_16") (pintype "output"))
      (node (ref "R+") (pin "1") (pinfunction "P_1") (pintype "passive"))
    )
    (net (code "71") (name "Net-(PAM1--OUT_R)") (class "Default")
      (node (ref "PAM1") (pin "14") (pinfunction "-OUT_R_14") (pintype "output"))
      (node (ref "R-") (pin "1") (pinfunction "P_1") (pintype "passive"))
    )
    (net (code "72") (name "Net-(PAM1-INL)") (class "Default")
      (node (ref "C14") (pin "2") (pinfunction "2_2") (pintype "passive"))
      (node (ref "PAM1") (pin "7") (pinfunction "INL_7") (pintype "input"))
    )
    (net (code "73") (name "Net-(PAM1-INR)") (class "Default")
      (node (ref "C13") (pin "2") (pinfunction "2_2") (pintype "passive"))
      (node (ref "PAM1") (pin "10") (pinfunction "INR_10") (pintype "output"))
    )
    (net (code "74") (name "Net-(PAM1-SHND)") (class "Default")
      (node (ref "J1") (pin "XIO-P4") (pinfunction "XIO-P4_XIO-P4") (pintype "passive"))
      (node (ref "PAM1") (pin "12") (pinfunction "SHND_12") (pintype "output"))
      (node (ref "R6") (pin "2") (pinfunction "2_2") (pintype "passive"))
    )
    (net (code "75") (name "Net-(PAM1-VREF)") (class "Default")
      (node (ref "C6") (pin "1") (pinfunction "1_1") (pintype "passive"))
      (node (ref "PAM1") (pin "8") (pinfunction "VREF_8") (pintype "input"))
    )
    (net (code "76") (name "Net-(PV-P)") (class "Default")
      (node (ref "PV") (pin "1") (pinfunction "P_1") (pintype "passive"))
      (node (ref "U$10") (pin "VIN") (pinfunction "VIN_VIN") (pintype "power_in"))
    )
    (net (code "77") (name "Net-(RI-P)") (class "Default")
      (node (ref "C13") (pin "1") (pinfunction "1_1") (pintype "passive"))
      (node (ref "R5") (pin "1") (pinfunction "1_1") (pintype "passive"))
      (node (ref "RI") (pin "1") (pinfunction "P_1") (pintype "passive"))
      (node (ref "RO") (pin "1") (pinfunction "P_1") (pintype "passive"))
    )
    (net (code "78") (name "VCC3V3") (class "Default")
      (node (ref "C9") (pin "1") (pinfunction "1_1") (pintype "passive"))
      (node (ref "IC1") (pin "5") (pinfunction "VCC_5") (pintype "power_in"))
      (node (ref "J1") (pin "VCC3V3") (pinfunction "VCC3V3_VCC3V3") (pintype "power_in"))
      (node (ref "R12") (pin "2") (pinfunction "2_2") (pintype "passive"))
      (node (ref "SDIO") (pin "4") (pinfunction "VDD_4") (pintype "power_in"))
      (node (ref "SJ3") (pin "1") (pinfunction "1_1") (pintype "passive"))
    )
    (net (code "79") (name "VCC5V") (class "Default")
      (node (ref "C10") (pin "1") (pinfunction "1_1") (pintype "passive"))
      (node (ref "C7") (pin "1") (pinfunction "1_1") (pintype "passive"))
      (node (ref "J1") (pin "VCC5V@1") (pinfunction "VCC-5V_VCC5V@1") (pintype "power_in"))
      (node (ref "SJ1") (pin "1") (pinfunction "1_1") (pintype "passive"))
      (node (ref "SJ3") (pin "3") (pinfunction "3_3") (pintype "passive"))
    )
    (net (code "80") (name "unconnected-(J1-PadAP-EINT1)") (class "Default")
      (node (ref "J1") (pin "AP-EINT1") (pinfunction "AP-EINT1_AP-EINT1") (pintype "passive"))
    )
    (net (code "81") (name "unconnected-(J1-PadCSID6)") (class "Default")
      (node (ref "J1") (pin "CSID6") (pinfunction "CSID6_CSID6") (pintype "passive"))
    )
    (net (code "82") (name "unconnected-(J1-PadCSID7)") (class "Default")
      (node (ref "J1") (pin "CSID7") (pinfunction "CSID7_CSID7") (pintype "passive"))
    )
    (net (code "83") (name "unconnected-(J1-PadMICIN1)") (class "Default")
      (node (ref "J1") (pin "MICIN1") (pinfunction "MICIN1_MICIN1") (pintype "passive"))
    )
    (net (code "84") (name "unconnected-(J1-PadMICM)") (class "Default")
      (node (ref "J1") (pin "MICM") (pinfunction "MICM_MICM") (pintype "passive"))
    )
    (net (code "85") (name "unconnected-(J1-PadTS)") (class "Default")
      (node (ref "J1") (pin "TS") (pinfunction "TS_TS") (pintype "passive"))
    )
    (net (code "86") (name "unconnected-(J1-PadXIO-P0)") (class "Default")
      (node (ref "J1") (pin "XIO-P0") (pinfunction "XIO-P0_XIO-P0") (pintype "passive"))
    )
    (net (code "87") (name "unconnected-(J1-PadXIO-P1)") (class "Default")
      (node (ref "J1") (pin "XIO-P1") (pinfunction "XIO-P1_XIO-P1") (pintype "passive"))
    )
    (net (code "88") (name "unconnected-(JP1-PadD+)") (class "Default")
      (node (ref "JP1") (pin "D+") (pinfunction "D+_D+") (pintype "bidirectional"))
    )
    (net (code "89") (name "unconnected-(JP1-PadD-)") (class "Default")
      (node (ref "JP1") (pin "D-") (pinfunction "D-_D-") (pintype "bidirectional"))
    )
    (net (code "90") (name "unconnected-(JP1-PadID)") (class "Default")
      (node (ref "JP1") (pin "ID") (pinfunction "ID_ID") (pintype "bidirectional"))
    )
    (net (code "91") (name "unconnected-(U2-NC-Pad3)") (class "Default")
      (node (ref "U2") (pin "3") (pinfunction "NC_3") (pintype "bidirectional"))
    )
    (net (code "92") (name "unconnected-(U2-NC-Pad4)") (class "Default")
      (node (ref "U2") (pin "4") (pinfunction "NC_4") (pintype "bidirectional"))
    )
    (net (code "93") (name "unconnected-(U2-NC-Pad5)") (class "Default")
      (node (ref "U2") (pin "5") (pinfunction "NC_5") (pintype "bidirectional"))
    )
    (net (code "94") (name "unconnected-(U2-NC-Pad6)") (class "Default")
      (node (ref "U2") (pin "6") (pinfunction "NC_6") (pintype "bidirectional"))
    )
    (net (code "95") (name "unconnected-(X1AC-1-Pad35)") (class "Default")
      (node (ref "X1") (pin "35") (pinfunction "1_35") (pintype "passive"))
    )
  )
)
